# LEDElement.net
KiCad netlist of a schematic drawn in Altium Designer
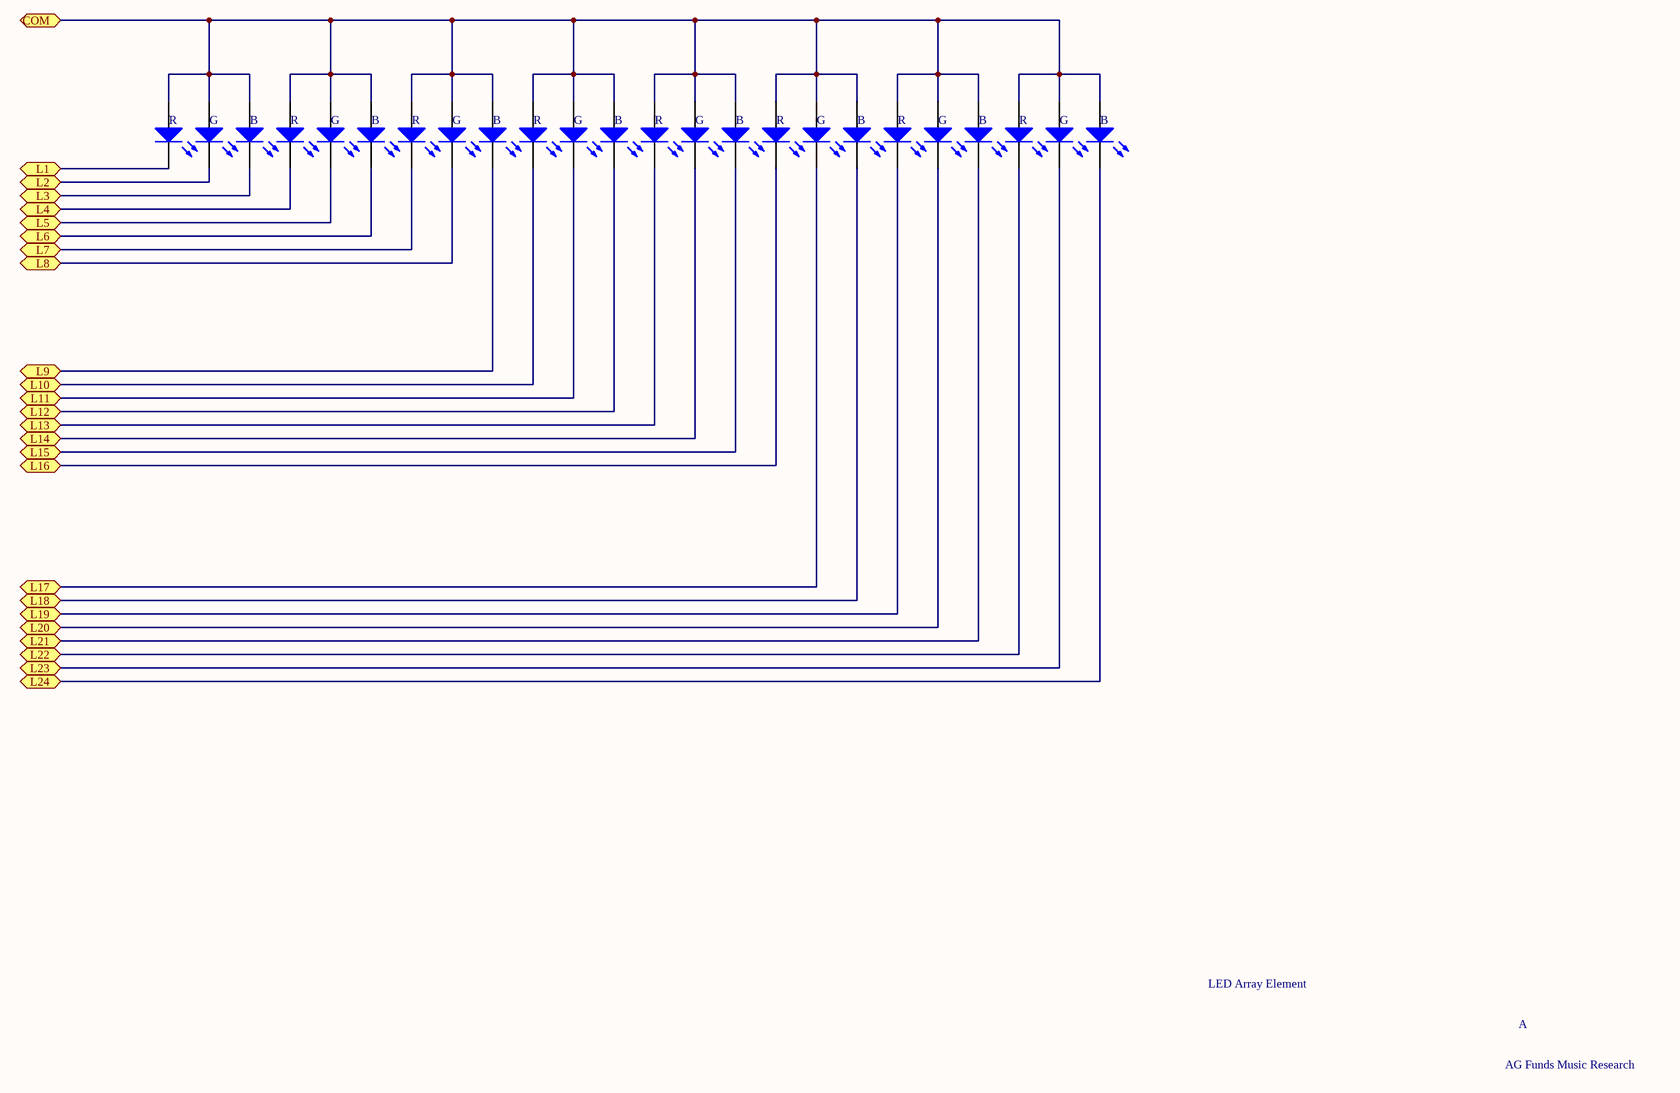
[diagram p0: LEDElement.SchDoc]

(export (version "E")
  (design (tool "Eeschema 10.0.6"))
  (components
    (comp (ref "LED1")
      (value "5050RGBLED")
      (footprint "5050 cRGBLED")
      (description "5050 RGB LED")
      (fields (field (name "PUBLISHER") "Altium Limited"))
      (libsource (lib "MIDIPiano") (part "5050RGBLED"))
    )
    (comp (ref "LED2")
      (value "5050RGBLED")
      (footprint "5050 cRGBLED")
      (description "5050 RGB LED")
      (fields (field (name "PUBLISHER") "Altium Limited"))
      (libsource (lib "MIDIPiano") (part "5050RGBLED"))
    )
    (comp (ref "LED3")
      (value "5050RGBLED")
      (footprint "5050 cRGBLED")
      (description "5050 RGB LED")
      (fields (field (name "PUBLISHER") "Altium Limited"))
      (libsource (lib "MIDIPiano") (part "5050RGBLED"))
    )
    (comp (ref "LED4")
      (value "5050RGBLED")
      (footprint "5050 cRGBLED")
      (description "5050 RGB LED")
      (fields (field (name "PUBLISHER") "Altium Limited"))
      (libsource (lib "MIDIPiano") (part "5050RGBLED"))
    )
    (comp (ref "LED5")
      (value "5050RGBLED")
      (footprint "5050 cRGBLED")
      (description "5050 RGB LED")
      (fields (field (name "PUBLISHER") "Altium Limited"))
      (libsource (lib "MIDIPiano") (part "5050RGBLED"))
    )
    (comp (ref "LED6")
      (value "5050RGBLED")
      (footprint "5050 cRGBLED")
      (description "5050 RGB LED")
      (fields (field (name "PUBLISHER") "Altium Limited"))
      (libsource (lib "MIDIPiano") (part "5050RGBLED"))
    )
    (comp (ref "LED7")
      (value "5050RGBLED")
      (footprint "5050 cRGBLED")
      (description "5050 RGB LED")
      (fields (field (name "PUBLISHER") "Altium Limited"))
      (libsource (lib "MIDIPiano") (part "5050RGBLED"))
    )
    (comp (ref "LED8")
      (value "5050RGBLED")
      (footprint "5050 cRGBLED")
      (description "5050 RGB LED")
      (fields (field (name "PUBLISHER") "Altium Limited"))
      (libsource (lib "MIDIPiano") (part "5050RGBLED"))
    )
  )
  (nets
    (net (code "1") (name "/COM") (class "Default")
      (node (ref "LED1") (pin "1") (pinfunction "A_1") (pintype "passive"))
      (node (ref "LED1") (pin "3") (pinfunction "A_3") (pintype "passive"))
      (node (ref "LED1") (pin "5") (pinfunction "A_5") (pintype "passive"))
      (node (ref "LED2") (pin "1") (pinfunction "A_1") (pintype "passive"))
      (node (ref "LED2") (pin "3") (pinfunction "A_3") (pintype "passive"))
      (node (ref "LED2") (pin "5") (pinfunction "A_5") (pintype "passive"))
      (node (ref "LED3") (pin "1") (pinfunction "A_1") (pintype "passive"))
      (node (ref "LED3") (pin "3") (pinfunction "A_3") (pintype "passive"))
      (node (ref "LED3") (pin "5") (pinfunction "A_5") (pintype "passive"))
      (node (ref "LED4") (pin "1") (pinfunction "A_1") (pintype "passive"))
      (node (ref "LED4") (pin "3") (pinfunction "A_3") (pintype "passive"))
      (node (ref "LED4") (pin "5") (pinfunction "A_5") (pintype "passive"))
      (node (ref "LED5") (pin "1") (pinfunction "A_1") (pintype "passive"))
      (node (ref "LED5") (pin "3") (pinfunction "A_3") (pintype "passive"))
      (node (ref "LED5") (pin "5") (pinfunction "A_5") (pintype "passive"))
      (node (ref "LED6") (pin "1") (pinfunction "A_1") (pintype "passive"))
      (node (ref "LED6") (pin "3") (pinfunction "A_3") (pintype "passive"))
      (node (ref "LED6") (pin "5") (pinfunction "A_5") (pintype "passive"))
      (node (ref "LED7") (pin "1") (pinfunction "A_1") (pintype "passive"))
      (node (ref "LED7") (pin "3") (pinfunction "A_3") (pintype "passive"))
      (node (ref "LED7") (pin "5") (pinfunction "A_5") (pintype "passive"))
      (node (ref "LED8") (pin "1") (pinfunction "A_1") (pintype "passive"))
      (node (ref "LED8") (pin "3") (pinfunction "A_3") (pintype "passive"))
      (node (ref "LED8") (pin "5") (pinfunction "A_5") (pintype "passive"))
    )
    (net (code "2") (name "/L1") (class "Default")
      (node (ref "LED1") (pin "6") (pinfunction "K_6") (pintype "passive"))
    )
    (net (code "3") (name "/L2") (class "Default")
      (node (ref "LED1") (pin "4") (pinfunction "K_4") (pintype "passive"))
    )
    (net (code "4") (name "/L3") (class "Default")
      (node (ref "LED1") (pin "2") (pinfunction "K_2") (pintype "passive"))
    )
    (net (code "5") (name "/L4") (class "Default")
      (node (ref "LED2") (pin "6") (pinfunction "K_6") (pintype "passive"))
    )
    (net (code "6") (name "/L5") (class "Default")
      (node (ref "LED2") (pin "4") (pinfunction "K_4") (pintype "passive"))
    )
    (net (code "7") (name "/L6") (class "Default")
      (node (ref "LED2") (pin "2") (pinfunction "K_2") (pintype "passive"))
    )
    (net (code "8") (name "/L7") (class "Default")
      (node (ref "LED3") (pin "6") (pinfunction "K_6") (pintype "passive"))
    )
    (net (code "9") (name "/L8") (class "Default")
      (node (ref "LED3") (pin "4") (pinfunction "K_4") (pintype "passive"))
    )
    (net (code "10") (name "/L9") (class "Default")
      (node (ref "LED3") (pin "2") (pinfunction "K_2") (pintype "passive"))
    )
    (net (code "11") (name "/L10") (class "Default")
      (node (ref "LED4") (pin "6") (pinfunction "K_6") (pintype "passive"))
    )
    (net (code "12") (name "/L11") (class "Default")
      (node (ref "LED4") (pin "4") (pinfunction "K_4") (pintype "passive"))
    )
    (net (code "13") (name "/L12") (class "Default")
      (node (ref "LED4") (pin "2") (pinfunction "K_2") (pintype "passive"))
    )
    (net (code "14") (name "/L13") (class "Default")
      (node (ref "LED5") (pin "6") (pinfunction "K_6") (pintype "passive"))
    )
    (net (code "15") (name "/L14") (class "Default")
      (node (ref "LED5") (pin "4") (pinfunction "K_4") (pintype "passive"))
    )
    (net (code "16") (name "/L15") (class "Default")
      (node (ref "LED5") (pin "2") (pinfunction "K_2") (pintype "passive"))
    )
    (net (code "17") (name "/L16") (class "Default")
      (node (ref "LED6") (pin "6") (pinfunction "K_6") (pintype "passive"))
    )
    (net (code "18") (name "/L17") (class "Default")
      (node (ref "LED6") (pin "4") (pinfunction "K_4") (pintype "passive"))
    )
    (net (code "19") (name "/L18") (class "Default")
      (node (ref "LED6") (pin "2") (pinfunction "K_2") (pintype "passive"))
    )
    (net (code "20") (name "/L19") (class "Default")
      (node (ref "LED7") (pin "6") (pinfunction "K_6") (pintype "passive"))
    )
    (net (code "21") (name "/L20") (class "Default")
      (node (ref "LED7") (pin "4") (pinfunction "K_4") (pintype "passive"))
    )
    (net (code "22") (name "/L21") (class "Default")
      (node (ref "LED7") (pin "2") (pinfunction "K_2") (pintype "passive"))
    )
    (net (code "23") (name "/L22") (class "Default")
      (node (ref "LED8") (pin "6") (pinfunction "K_6") (pintype "passive"))
    )
    (net (code "24") (name "/L23") (class "Default")
      (node (ref "LED8") (pin "4") (pinfunction "K_4") (pintype "passive"))
    )
    (net (code "25") (name "/L24") (class "Default")
      (node (ref "LED8") (pin "2") (pinfunction "K_2") (pintype "passive"))
    )
  )
)
